# BT_AQ_DOL_R8.net
KiCad netlist of a schematic drawn in EAGLE
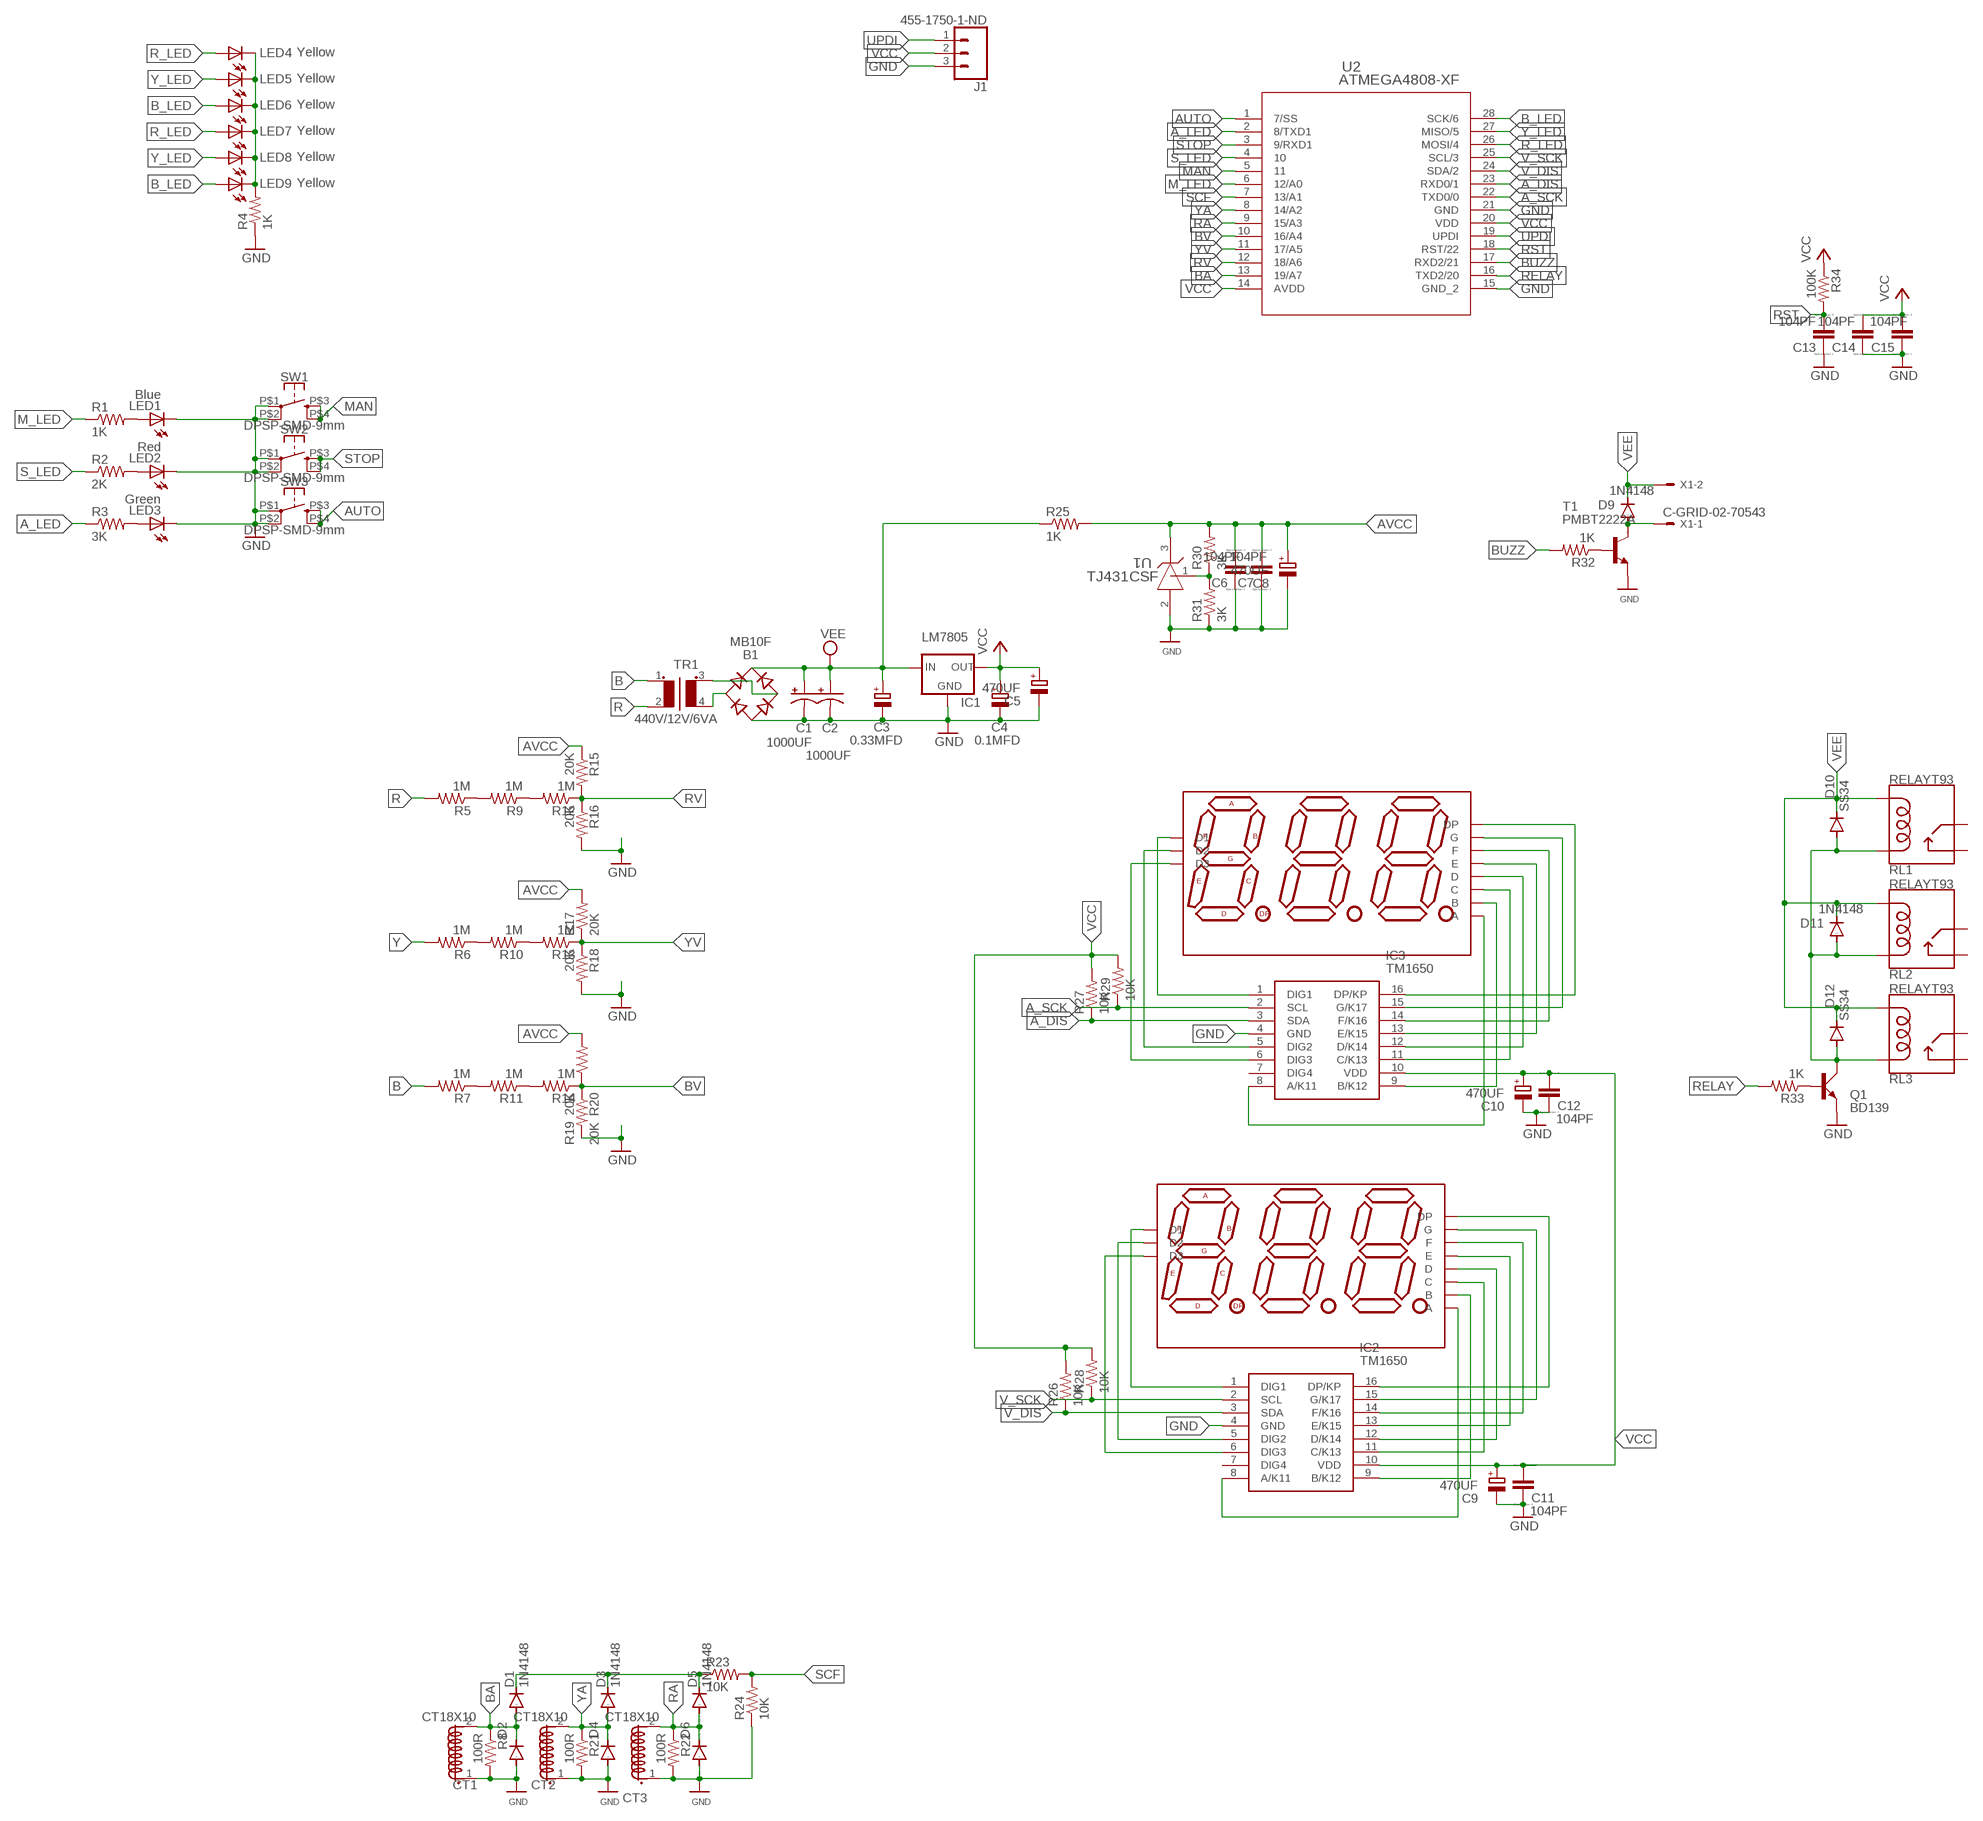
[diagram p0: schematic, sheet 1]

(export (version "E")
  (design (tool "Eeschema 10.0.6"))
  (components
    (comp (ref "B1")
      (value "MB10F")
      (footprint "eagle-import:SOIC-4")
      (libsource (lib "eagle-import") (part "MBS8"))
    )
    (comp (ref "C1")
      (value "1000UF")
      (footprint "eagle-import:E3,5-10")
      (libsource (lib "eagle-import") (part "CPOL-USE3.5-10"))
    )
    (comp (ref "C2")
      (value "1000UF")
      (footprint "eagle-import:E3,5-10")
      (libsource (lib "eagle-import") (part "CPOL-USE3.5-10"))
    )
    (comp (ref "C3")
      (value "0.33MFD")
      (footprint "eagle-import:E2,5-5")
      (libsource (lib "eagle-import") (part "CPOL-EUE2.5-5"))
    )
    (comp (ref "C4")
      (value "0.1MFD")
      (footprint "eagle-import:E2,5-5")
      (libsource (lib "eagle-import") (part "CPOL-EUE2.5-5"))
    )
    (comp (ref "C5")
      (value "470UF")
      (footprint "eagle-import:E3,5-8")
      (libsource (lib "eagle-import") (part "CPOL-EUE3.5-8"))
    )
    (comp (ref "C6")
      (value "104PF")
      (footprint "eagle-import:C1206")
      (libsource (lib "eagle-import") (part "CC1206"))
    )
    (comp (ref "C7")
      (value "104PF")
      (footprint "eagle-import:C1206")
      (libsource (lib "eagle-import") (part "CC1206"))
    )
    (comp (ref "C8")
      (value "470UF")
      (footprint "eagle-import:E3,5-8")
      (libsource (lib "eagle-import") (part "CPOL-EUE3.5-8"))
    )
    (comp (ref "C9")
      (value "470UF")
      (footprint "eagle-import:E3,5-8")
      (libsource (lib "eagle-import") (part "CPOL-EUE3.5-8"))
    )
    (comp (ref "C10")
      (value "470UF")
      (footprint "eagle-import:E3,5-8")
      (libsource (lib "eagle-import") (part "CPOL-EUE3.5-8"))
    )
    (comp (ref "C11")
      (value "104PF")
      (footprint "eagle-import:C1206")
      (libsource (lib "eagle-import") (part "CC1206"))
    )
    (comp (ref "C12")
      (value "104PF")
      (footprint "eagle-import:C1206")
      (libsource (lib "eagle-import") (part "CC1206"))
    )
    (comp (ref "C13")
      (value "104PF")
      (footprint "eagle-import:C1206")
      (libsource (lib "eagle-import") (part "CC1206"))
    )
    (comp (ref "C14")
      (value "104PF")
      (footprint "eagle-import:C1206")
      (libsource (lib "eagle-import") (part "CC1206"))
    )
    (comp (ref "C15")
      (value "104PF")
      (footprint "eagle-import:C1206")
      (libsource (lib "eagle-import") (part "CC1206"))
    )
    (comp (ref "CT1")
      (value "CT18X10")
      (footprint "eagle-import:ZMCT103C")
      (libsource (lib "eagle-import") (part "CT18X10"))
    )
    (comp (ref "CT2")
      (value "CT18X10")
      (footprint "eagle-import:ZMCT103C")
      (libsource (lib "eagle-import") (part "CT18X10"))
    )
    (comp (ref "CT3")
      (value "CT18X10")
      (footprint "eagle-import:ZMCT103C")
      (libsource (lib "eagle-import") (part "CT18X10"))
    )
    (comp (ref "D1")
      (value "1N4148")
      (footprint "eagle-import:MINIMELF")
      (libsource (lib "eagle-import") (part "DIODE-MINIMELF"))
    )
    (comp (ref "D2")
      (value "SMAJ12A")
      (footprint "eagle-import:DO214AC")
      (libsource (lib "eagle-import") (part "DIODE-DO214AC"))
    )
    (comp (ref "D3")
      (value "1N4148")
      (footprint "eagle-import:MINIMELF")
      (libsource (lib "eagle-import") (part "DIODE-MINIMELF"))
    )
    (comp (ref "D4")
      (value "SMAJ12A")
      (footprint "eagle-import:DO214AC")
      (libsource (lib "eagle-import") (part "DIODE-DO214AC"))
    )
    (comp (ref "D5")
      (value "1N4148")
      (footprint "eagle-import:MINIMELF")
      (libsource (lib "eagle-import") (part "DIODE-MINIMELF"))
    )
    (comp (ref "D6")
      (value "SMAJ12A")
      (footprint "eagle-import:DO214AC")
      (libsource (lib "eagle-import") (part "DIODE-DO214AC"))
    )
    (comp (ref "D7")
      (value "SUNR036CC3D")
      (footprint "eagle-import:7S3D036_DIP")
      (libsource (lib "eagle-import") (part "7SEGMENT-3DIGITDIP"))
    )
    (comp (ref "D8")
      (value "SUNR036CC3D")
      (footprint "eagle-import:7S3D036_DIP")
      (libsource (lib "eagle-import") (part "7SEGMENT-3DIGITDIP"))
    )
    (comp (ref "D9")
      (value "1N4148")
      (footprint "eagle-import:MINIMELF")
      (libsource (lib "eagle-import") (part "DIODE-MINIMELF"))
    )
    (comp (ref "D10")
      (value "SS34")
      (footprint "eagle-import:DO-214AC")
      (libsource (lib "eagle-import") (part "DIODE-DO-214AC"))
    )
    (comp (ref "D11")
      (value "1N4148")
      (footprint "eagle-import:MINIMELF")
      (libsource (lib "eagle-import") (part "DIODE-MINIMELF"))
    )
    (comp (ref "D12")
      (value "SS34")
      (footprint "eagle-import:DO-214AC")
      (libsource (lib "eagle-import") (part "DIODE-DO-214AC"))
    )
    (comp (ref "IC1")
      (value "LM7805")
      (footprint "eagle-import:78XXS")
      (libsource (lib "eagle-import") (part "78XXS"))
    )
    (comp (ref "IC2")
      (value "TM1650")
      (footprint "eagle-import:SOIC127P604X185-16N")
      (fields (field (name "MANUFACTURER_PART_NUMBER") "tm1650"))
      (libsource (lib "eagle-import") (part "TM1650"))
    )
    (comp (ref "IC3")
      (value "TM1650")
      (footprint "eagle-import:SOIC127P604X185-16N")
      (fields (field (name "MANUFACTURER_PART_NUMBER") "tm1650"))
      (libsource (lib "eagle-import") (part "TM1650"))
    )
    (comp (ref "J1")
      (value "455-1750-1-ND")
      (footprint "eagle-import:1X03")
      (libsource (lib "eagle-import") (part "CONN_03"))
    )
    (comp (ref "LED1")
      (value "Blue")
      (footprint "eagle-import:LED3MM")
      (libsource (lib "eagle-import") (part "LED3MM"))
    )
    (comp (ref "LED2")
      (value "Red")
      (footprint "eagle-import:LED3MM")
      (libsource (lib "eagle-import") (part "LED3MM"))
    )
    (comp (ref "LED3")
      (value "Green")
      (footprint "eagle-import:LED3MM")
      (libsource (lib "eagle-import") (part "LED3MM"))
    )
    (comp (ref "LED4")
      (value "Yellow")
      (footprint "eagle-import:LED3MM")
      (libsource (lib "eagle-import") (part "LED3MM"))
    )
    (comp (ref "LED5")
      (value "Yellow")
      (footprint "eagle-import:LED3MM")
      (libsource (lib "eagle-import") (part "LED3MM"))
    )
    (comp (ref "LED6")
      (value "Yellow")
      (footprint "eagle-import:LED3MM")
      (libsource (lib "eagle-import") (part "LED3MM"))
    )
    (comp (ref "LED7")
      (value "Yellow")
      (footprint "eagle-import:LED3MM")
      (libsource (lib "eagle-import") (part "LED3MM"))
    )
    (comp (ref "LED8")
      (value "Yellow")
      (footprint "eagle-import:LED3MM")
      (libsource (lib "eagle-import") (part "LED3MM"))
    )
    (comp (ref "LED9")
      (value "Yellow")
      (footprint "eagle-import:LED3MM")
      (libsource (lib "eagle-import") (part "LED3MM"))
    )
    (comp (ref "Q1")
      (value "BD139")
      (footprint "eagle-import:TO126AV")
      (libsource (lib "eagle-import") (part "BD139"))
    )
    (comp (ref "R1")
      (value "1K")
      (footprint "eagle-import:M1206")
      (libsource (lib "eagle-import") (part "rcl_334_R-US_M1206"))
    )
    (comp (ref "R2")
      (value "2K")
      (footprint "eagle-import:M1206")
      (libsource (lib "eagle-import") (part "rcl_334_R-US_M1206"))
    )
    (comp (ref "R3")
      (value "3K")
      (footprint "eagle-import:M1206")
      (libsource (lib "eagle-import") (part "rcl_334_R-US_M1206"))
    )
    (comp (ref "R4")
      (value "1K")
      (footprint "eagle-import:M1206")
      (libsource (lib "eagle-import") (part "rcl_334_R-US_M1206"))
    )
    (comp (ref "R5")
      (value "1M")
      (footprint "eagle-import:M1206")
      (libsource (lib "eagle-import") (part "rcl_334_R-US_M1206"))
    )
    (comp (ref "R6")
      (value "1M")
      (footprint "eagle-import:M1206")
      (libsource (lib "eagle-import") (part "rcl_334_R-US_M1206"))
    )
    (comp (ref "R7")
      (value "1M")
      (footprint "eagle-import:M1206")
      (libsource (lib "eagle-import") (part "rcl_334_R-US_M1206"))
    )
    (comp (ref "R8")
      (value "100R")
      (footprint "eagle-import:M1206")
      (libsource (lib "eagle-import") (part "R-US_M1206"))
    )
    (comp (ref "R9")
      (value "1M")
      (footprint "eagle-import:M1206")
      (libsource (lib "eagle-import") (part "rcl_334_R-US_M1206"))
    )
    (comp (ref "R10")
      (value "1M")
      (footprint "eagle-import:M1206")
      (libsource (lib "eagle-import") (part "rcl_334_R-US_M1206"))
    )
    (comp (ref "R11")
      (value "1M")
      (footprint "eagle-import:M1206")
      (libsource (lib "eagle-import") (part "rcl_334_R-US_M1206"))
    )
    (comp (ref "R12")
      (value "1M")
      (footprint "eagle-import:M1206")
      (libsource (lib "eagle-import") (part "rcl_334_R-US_M1206"))
    )
    (comp (ref "R13")
      (value "1M")
      (footprint "eagle-import:M1206")
      (libsource (lib "eagle-import") (part "rcl_334_R-US_M1206"))
    )
    (comp (ref "R14")
      (value "1M")
      (footprint "eagle-import:M1206")
      (libsource (lib "eagle-import") (part "rcl_334_R-US_M1206"))
    )
    (comp (ref "R15")
      (value "20K")
      (footprint "eagle-import:M1206")
      (libsource (lib "eagle-import") (part "rcl_334_R-US_M1206"))
    )
    (comp (ref "R16")
      (value "20K")
      (footprint "eagle-import:M1206")
      (libsource (lib "eagle-import") (part "rcl_334_R-US_M1206"))
    )
    (comp (ref "R17")
      (value "20K")
      (footprint "eagle-import:M1206")
      (libsource (lib "eagle-import") (part "rcl_334_R-US_M1206"))
    )
    (comp (ref "R18")
      (value "20K")
      (footprint "eagle-import:M1206")
      (libsource (lib "eagle-import") (part "rcl_334_R-US_M1206"))
    )
    (comp (ref "R19")
      (value "20K")
      (footprint "eagle-import:M1206")
      (libsource (lib "eagle-import") (part "rcl_334_R-US_M1206"))
    )
    (comp (ref "R20")
      (value "20K")
      (footprint "eagle-import:M1206")
      (libsource (lib "eagle-import") (part "rcl_334_R-US_M1206"))
    )
    (comp (ref "R21")
      (value "100R")
      (footprint "eagle-import:M1206")
      (libsource (lib "eagle-import") (part "R-US_M1206"))
    )
    (comp (ref "R22")
      (value "100R")
      (footprint "eagle-import:M1206")
      (libsource (lib "eagle-import") (part "R-US_M1206"))
    )
    (comp (ref "R23")
      (value "10K")
      (footprint "eagle-import:M1206")
      (libsource (lib "eagle-import") (part "R-US_M1206"))
    )
    (comp (ref "R24")
      (value "10K")
      (footprint "eagle-import:M1206")
      (libsource (lib "eagle-import") (part "R-US_M1206"))
    )
    (comp (ref "R25")
      (value "1K")
      (footprint "eagle-import:M1206")
      (libsource (lib "eagle-import") (part "R-US_M1206"))
    )
    (comp (ref "R26")
      (value "10K")
      (footprint "eagle-import:M1206")
      (libsource (lib "eagle-import") (part "rcl_334_R-US_M1206"))
    )
    (comp (ref "R27")
      (value "10K")
      (footprint "eagle-import:M1206")
      (libsource (lib "eagle-import") (part "rcl_334_R-US_M1206"))
    )
    (comp (ref "R28")
      (value "10K")
      (footprint "eagle-import:M1206")
      (libsource (lib "eagle-import") (part "rcl_334_R-US_M1206"))
    )
    (comp (ref "R29")
      (value "10K")
      (footprint "eagle-import:M1206")
      (libsource (lib "eagle-import") (part "rcl_334_R-US_M1206"))
    )
    (comp (ref "R30")
      (value "3K")
      (footprint "eagle-import:M1206")
      (libsource (lib "eagle-import") (part "R-US_M1206"))
    )
    (comp (ref "R31")
      (value "3K")
      (footprint "eagle-import:M1206")
      (libsource (lib "eagle-import") (part "R-US_M1206"))
    )
    (comp (ref "R32")
      (value "1K")
      (footprint "eagle-import:M1206")
      (libsource (lib "eagle-import") (part "rcl_334_R-US_M1206"))
    )
    (comp (ref "R33")
      (value "1K")
      (footprint "eagle-import:M1206")
      (libsource (lib "eagle-import") (part "rcl_334_R-US_M1206"))
    )
    (comp (ref "R34")
      (value "100K")
      (footprint "eagle-import:M1206")
      (libsource (lib "eagle-import") (part "rcl_334_R-US_M1206"))
    )
    (comp (ref "RL1")
      (value "RELAYT93")
      (footprint "eagle-import:DT93")
      (libsource (lib "eagle-import") (part "RELAYT93"))
    )
    (comp (ref "RL2")
      (value "RELAYT93")
      (footprint "eagle-import:DT93")
      (libsource (lib "eagle-import") (part "RELAYT93"))
    )
    (comp (ref "RL3")
      (value "RELAYT93")
      (footprint "eagle-import:DT93")
      (libsource (lib "eagle-import") (part "RELAYT93"))
    )
    (comp (ref "SW1")
      (value "DPSP-SMD-9mm")
      (footprint "eagle-import:B3F-40XX-ROUND-SMD")
      (libsource (lib "eagle-import") (part "DPSP-SMD"))
    )
    (comp (ref "SW2")
      (value "DPSP-SMD-9mm")
      (footprint "eagle-import:B3F-40XX-ROUND-SMD")
      (libsource (lib "eagle-import") (part "DPSP-SMD"))
    )
    (comp (ref "SW3")
      (value "DPSP-SMD-9mm")
      (footprint "eagle-import:B3F-40XX-ROUND-SMD")
      (libsource (lib "eagle-import") (part "DPSP-SMD"))
    )
    (comp (ref "T1")
      (value "PMBT2222A")
      (footprint "eagle-import:SC59-BEC")
      (libsource (lib "eagle-import") (part "-NPN-SC59-BECMMUN2213LT1"))
    )
    (comp (ref "TR1")
      (value "440V/12V/6VA")
      (footprint "eagle-import:440V12V6VA")
      (libsource (lib "eagle-import") (part "TRANSFORMER6VA"))
    )
    (comp (ref "U1")
      (value "TJ431CSF")
      (footprint "eagle-import:SOT-23")
      (fields
        (field (name "MANUFACTURER_PART_NUMBER") "TL431IDBZTG4")
        (field (name "COPYRIGHT") "Copyright (C) 2022 Ultra Librarian. All rights reserved.")
      )
      (libsource (lib "eagle-import") (part "TJ431CSFDBZ0003A_L"))
    )
    (comp (ref "U2")
      (value "ATMEGA4808-XF")
      (footprint "eagle-import:SSOP28_SS_MCH")
      (fields (field (name "COPYRIGHT") "Copyright (C) 2022 Ultra Librarian. All rights reserved."))
      (libsource (lib "eagle-import") (part "ATMEGA4808-XF"))
    )
    (comp (ref "X1")
      (value "C-GRID-02-70543")
      (footprint "eagle-import:70543-02")
      (fields (field (name "MF") "MOLEX"))
      (libsource (lib "eagle-import") (part "C-GRID-02-70543"))
    )
  )
  (nets
    (net (code "1") (name "AUTO") (class "Default")
      (node (ref "SW3") (pin "P$3") (pinfunction "3_P$3") (pintype "passive"))
      (node (ref "SW3") (pin "P$4") (pinfunction "4_P$4") (pintype "passive"))
      (node (ref "U2") (pin "1") (pinfunction "7/SS_1") (pintype "bidirectional"))
    )
    (net (code "2") (name "AVCC") (class "Default")
      (node (ref "C6") (pin "2") (pinfunction "2_2") (pintype "passive"))
      (node (ref "C7") (pin "2") (pinfunction "2_2") (pintype "passive"))
      (node (ref "C8") (pin "+") (pinfunction "+_+") (pintype "passive"))
      (node (ref "R15") (pin "1") (pinfunction "1_1") (pintype "passive"))
      (node (ref "R17") (pin "2") (pinfunction "2_2") (pintype "passive"))
      (node (ref "R19") (pin "2") (pinfunction "2_2") (pintype "passive"))
      (node (ref "R25") (pin "2") (pinfunction "2_2") (pintype "passive"))
      (node (ref "R30") (pin "2") (pinfunction "2_2") (pintype "passive"))
      (node (ref "U1") (pin "3") (pinfunction "CATHODE_3") (pintype "passive"))
    )
    (net (code "3") (name "A_DIS") (class "Default")
      (node (ref "IC3") (pin "3") (pinfunction "SDA_3") (pintype "input"))
      (node (ref "R27") (pin "1") (pinfunction "1_1") (pintype "passive"))
      (node (ref "U2") (pin "23") (pinfunction "RXD0/1_23") (pintype "bidirectional"))
    )
    (net (code "4") (name "A_LED") (class "Default")
      (node (ref "R3") (pin "1") (pinfunction "1_1") (pintype "passive"))
      (node (ref "U2") (pin "2") (pinfunction "8/TXD1_2") (pintype "bidirectional"))
    )
    (net (code "5") (name "A_SCK") (class "Default")
      (node (ref "IC3") (pin "2") (pinfunction "SCL_2") (pintype "input"))
      (node (ref "R29") (pin "1") (pinfunction "1_1") (pintype "passive"))
      (node (ref "U2") (pin "22") (pinfunction "TXD0/0_22") (pintype "bidirectional"))
    )
    (net (code "6") (name "B") (class "Default")
      (node (ref "R7") (pin "2") (pinfunction "2_2") (pintype "passive"))
      (node (ref "TR1") (pin "1") (pinfunction "P1_1") (pintype "passive"))
    )
    (net (code "7") (name "BA") (class "Default")
      (node (ref "CT1") (pin "2") (pinfunction "S1.2_2") (pintype "passive"))
      (node (ref "D1") (pin "A") (pinfunction "A_A") (pintype "passive"))
      (node (ref "D2") (pin "C") (pinfunction "C_C") (pintype "passive"))
      (node (ref "R8") (pin "1") (pinfunction "1_1") (pintype "passive"))
      (node (ref "U2") (pin "13") (pinfunction "19/A7_13") (pintype "bidirectional"))
    )
    (net (code "8") (name "BUZZ") (class "Default")
      (node (ref "R32") (pin "2") (pinfunction "2_2") (pintype "passive"))
      (node (ref "U2") (pin "17") (pinfunction "RXD2/21_17") (pintype "bidirectional"))
    )
    (net (code "9") (name "BV") (class "Default")
      (node (ref "R14") (pin "1") (pinfunction "1_1") (pintype "passive"))
      (node (ref "R19") (pin "1") (pinfunction "1_1") (pintype "passive"))
      (node (ref "R20") (pin "1") (pinfunction "1_1") (pintype "passive"))
      (node (ref "U2") (pin "10") (pinfunction "16/A4_10") (pintype "bidirectional"))
    )
    (net (code "10") (name "B_LED") (class "Default")
      (node (ref "LED6") (pin "A") (pinfunction "A_A") (pintype "passive"))
      (node (ref "LED9") (pin "A") (pinfunction "A_A") (pintype "passive"))
      (node (ref "U2") (pin "28") (pinfunction "SCK/6_28") (pintype "bidirectional"))
    )
    (net (code "11") (name "GND") (class "Default")
      (node (ref "B1") (pin "-") (pinfunction "-_-") (pintype "passive"))
      (node (ref "C1") (pin "-") (pinfunction "-_-") (pintype "passive"))
      (node (ref "C10") (pin "-") (pinfunction "-_-") (pintype "passive"))
      (node (ref "C11") (pin "1") (pinfunction "1_1") (pintype "passive"))
      (node (ref "C12") (pin "1") (pinfunction "1_1") (pintype "passive"))
      (node (ref "C13") (pin "1") (pinfunction "1_1") (pintype "passive"))
      (node (ref "C14") (pin "1") (pinfunction "1_1") (pintype "passive"))
      (node (ref "C15") (pin "1") (pinfunction "1_1") (pintype "passive"))
      (node (ref "C2") (pin "-") (pinfunction "-_-") (pintype "passive"))
      (node (ref "C3") (pin "-") (pinfunction "-_-") (pintype "passive"))
      (node (ref "C4") (pin "-") (pinfunction "-_-") (pintype "passive"))
      (node (ref "C5") (pin "-") (pinfunction "-_-") (pintype "passive"))
      (node (ref "C6") (pin "1") (pinfunction "1_1") (pintype "passive"))
      (node (ref "C7") (pin "1") (pinfunction "1_1") (pintype "passive"))
      (node (ref "C8") (pin "-") (pinfunction "-_-") (pintype "passive"))
      (node (ref "C9") (pin "-") (pinfunction "-_-") (pintype "passive"))
      (node (ref "CT1") (pin "1") (pinfunction "S1.1_1") (pintype "passive"))
      (node (ref "CT2") (pin "1") (pinfunction "S1.1_1") (pintype "passive"))
      (node (ref "CT3") (pin "1") (pinfunction "S1.1_1") (pintype "passive"))
      (node (ref "D2") (pin "A") (pinfunction "A_A") (pintype "passive"))
      (node (ref "D4") (pin "A") (pinfunction "A_A") (pintype "passive"))
      (node (ref "D6") (pin "A") (pinfunction "A_A") (pintype "passive"))
      (node (ref "IC1") (pin "GND") (pinfunction "GND_GND") (pintype "input"))
      (node (ref "IC2") (pin "4") (pinfunction "GND_4") (pintype "power_in"))
      (node (ref "IC3") (pin "4") (pinfunction "GND_4") (pintype "power_in"))
      (node (ref "J1") (pin "3") (pinfunction "3_3") (pintype "passive"))
      (node (ref "LED1") (pin "K") (pinfunction "C_K") (pintype "passive"))
      (node (ref "LED2") (pin "K") (pinfunction "C_K") (pintype "passive"))
      (node (ref "LED3") (pin "K") (pinfunction "C_K") (pintype "passive"))
      (node (ref "Q1") (pin "E") (pinfunction "E_E") (pintype "passive"))
      (node (ref "R16") (pin "2") (pinfunction "2_2") (pintype "passive"))
      (node (ref "R18") (pin "2") (pinfunction "2_2") (pintype "passive"))
      (node (ref "R20") (pin "2") (pinfunction "2_2") (pintype "passive"))
      (node (ref "R21") (pin "2") (pinfunction "2_2") (pintype "passive"))
      (node (ref "R22") (pin "2") (pinfunction "2_2") (pintype "passive"))
      (node (ref "R24") (pin "1") (pinfunction "1_1") (pintype "passive"))
      (node (ref "R31") (pin "1") (pinfunction "1_1") (pintype "passive"))
      (node (ref "R4") (pin "1") (pinfunction "1_1") (pintype "passive"))
      (node (ref "R8") (pin "2") (pinfunction "2_2") (pintype "passive"))
      (node (ref "SW1") (pin "P$1") (pinfunction "1_P$1") (pintype "passive"))
      (node (ref "SW1") (pin "P$2") (pinfunction "2_P$2") (pintype "passive"))
      (node (ref "SW2") (pin "P$1") (pinfunction "1_P$1") (pintype "passive"))
      (node (ref "SW2") (pin "P$2") (pinfunction "2_P$2") (pintype "passive"))
      (node (ref "SW3") (pin "P$1") (pinfunction "1_P$1") (pintype "passive"))
      (node (ref "SW3") (pin "P$2") (pinfunction "2_P$2") (pintype "passive"))
      (node (ref "T1") (pin "E") (pinfunction "E_E") (pintype "passive"))
      (node (ref "U1") (pin "2") (pinfunction "ANODE_2") (pintype "passive"))
      (node (ref "U2") (pin "15") (pinfunction "GND_2_15") (pintype "passive"))
      (node (ref "U2") (pin "21") (pinfunction "GND_21") (pintype "passive"))
    )
    (net (code "12") (name "MAN") (class "Default")
      (node (ref "SW1") (pin "P$3") (pinfunction "3_P$3") (pintype "passive"))
      (node (ref "SW1") (pin "P$4") (pinfunction "4_P$4") (pintype "passive"))
      (node (ref "U2") (pin "5") (pinfunction "11_5") (pintype "bidirectional"))
    )
    (net (code "13") (name "M_LED") (class "Default")
      (node (ref "R1") (pin "1") (pinfunction "1_1") (pintype "passive"))
      (node (ref "U2") (pin "6") (pinfunction "12/A0_6") (pintype "bidirectional"))
    )
    (net (code "14") (name "Net-(B1-AC1)") (class "Default")
      (node (ref "B1") (pin "~1") (pinfunction "AC1_~1") (pintype "passive"))
      (node (ref "TR1") (pin "4") (pinfunction "S2_4") (pintype "passive"))
    )
    (net (code "15") (name "Net-(B1-AC2)") (class "Default")
      (node (ref "B1") (pin "~2") (pinfunction "AC2_~2") (pintype "passive"))
      (node (ref "TR1") (pin "3") (pinfunction "S1_3") (pintype "passive"))
    )
    (net (code "16") (name "Net-(D1-PadC)") (class "Default")
      (node (ref "D1") (pin "C") (pinfunction "C_C") (pintype "passive"))
      (node (ref "D3") (pin "C") (pinfunction "C_C") (pintype "passive"))
      (node (ref "D5") (pin "C") (pinfunction "C_C") (pintype "passive"))
      (node (ref "R23") (pin "1") (pinfunction "1_1") (pintype "passive"))
    )
    (net (code "17") (name "Net-(D7-A)") (class "Default")
      (node (ref "D7") (pin "11") (pinfunction "A_11") (pintype "bidirectional"))
      (node (ref "IC2") (pin "8") (pinfunction "A/K11_8") (pintype "bidirectional"))
    )
    (net (code "18") (name "Net-(D7-B)") (class "Default")
      (node (ref "D7") (pin "7") (pinfunction "B_7") (pintype "bidirectional"))
      (node (ref "IC2") (pin "9") (pinfunction "B/K12_9") (pintype "bidirectional"))
    )
    (net (code "19") (name "Net-(D7-C)") (class "Default")
      (node (ref "D7") (pin "4") (pinfunction "C_4") (pintype "bidirectional"))
      (node (ref "IC2") (pin "11") (pinfunction "C/K13_11") (pintype "bidirectional"))
    )
    (net (code "20") (name "Net-(D7-D)") (class "Default")
      (node (ref "D7") (pin "2") (pinfunction "D_2") (pintype "bidirectional"))
      (node (ref "IC2") (pin "12") (pinfunction "D/K14_12") (pintype "bidirectional"))
    )
    (net (code "21") (name "Net-(D7-D1)") (class "Default")
      (node (ref "D7") (pin "12") (pinfunction "D1_12") (pintype "bidirectional"))
      (node (ref "IC2") (pin "1") (pinfunction "DIG1_1") (pintype "bidirectional"))
    )
    (net (code "22") (name "Net-(D7-D2)") (class "Default")
      (node (ref "D7") (pin "9") (pinfunction "D2_9") (pintype "bidirectional"))
      (node (ref "IC2") (pin "5") (pinfunction "DIG2_5") (pintype "bidirectional"))
    )
    (net (code "23") (name "Net-(D7-D3)") (class "Default")
      (node (ref "D7") (pin "8") (pinfunction "D3_8") (pintype "bidirectional"))
      (node (ref "IC2") (pin "6") (pinfunction "DIG3_6") (pintype "bidirectional"))
    )
    (net (code "24") (name "Net-(D7-DP)") (class "Default")
      (node (ref "D7") (pin "3") (pinfunction "DP_3") (pintype "bidirectional"))
      (node (ref "IC2") (pin "16") (pinfunction "DP/KP_16") (pintype "bidirectional"))
    )
    (net (code "25") (name "Net-(D7-E)") (class "Default")
      (node (ref "D7") (pin "1") (pinfunction "E_1") (pintype "bidirectional"))
      (node (ref "IC2") (pin "13") (pinfunction "E/K15_13") (pintype "bidirectional"))
    )
    (net (code "26") (name "Net-(D7-F)") (class "Default")
      (node (ref "D7") (pin "10") (pinfunction "F_10") (pintype "bidirectional"))
      (node (ref "IC2") (pin "14") (pinfunction "F/K16_14") (pintype "bidirectional"))
    )
    (net (code "27") (name "Net-(D7-G)") (class "Default")
      (node (ref "D7") (pin "5") (pinfunction "G_5") (pintype "bidirectional"))
      (node (ref "IC2") (pin "15") (pinfunction "G/K17_15") (pintype "bidirectional"))
    )
    (net (code "28") (name "Net-(D8-A)") (class "Default")
      (node (ref "D8") (pin "11") (pinfunction "A_11") (pintype "bidirectional"))
      (node (ref "IC3") (pin "8") (pinfunction "A/K11_8") (pintype "bidirectional"))
    )
    (net (code "29") (name "Net-(D8-B)") (class "Default")
      (node (ref "D8") (pin "7") (pinfunction "B_7") (pintype "bidirectional"))
      (node (ref "IC3") (pin "9") (pinfunction "B/K12_9") (pintype "bidirectional"))
    )
    (net (code "30") (name "Net-(D8-C)") (class "Default")
      (node (ref "D8") (pin "4") (pinfunction "C_4") (pintype "bidirectional"))
      (node (ref "IC3") (pin "11") (pinfunction "C/K13_11") (pintype "bidirectional"))
    )
    (net (code "31") (name "Net-(D8-D)") (class "Default")
      (node (ref "D8") (pin "2") (pinfunction "D_2") (pintype "bidirectional"))
      (node (ref "IC3") (pin "12") (pinfunction "D/K14_12") (pintype "bidirectional"))
    )
    (net (code "32") (name "Net-(D8-D1)") (class "Default")
      (node (ref "D8") (pin "12") (pinfunction "D1_12") (pintype "bidirectional"))
      (node (ref "IC3") (pin "1") (pinfunction "DIG1_1") (pintype "bidirectional"))
    )
    (net (code "33") (name "Net-(D8-D2)") (class "Default")
      (node (ref "D8") (pin "9") (pinfunction "D2_9") (pintype "bidirectional"))
      (node (ref "IC3") (pin "5") (pinfunction "DIG2_5") (pintype "bidirectional"))
    )
    (net (code "34") (name "Net-(D8-D3)") (class "Default")
      (node (ref "D8") (pin "8") (pinfunction "D3_8") (pintype "bidirectional"))
      (node (ref "IC3") (pin "6") (pinfunction "DIG3_6") (pintype "bidirectional"))
    )
    (net (code "35") (name "Net-(D8-DP)") (class "Default")
      (node (ref "D8") (pin "3") (pinfunction "DP_3") (pintype "bidirectional"))
      (node (ref "IC3") (pin "16") (pinfunction "DP/KP_16") (pintype "bidirectional"))
    )
    (net (code "36") (name "Net-(D8-E)") (class "Default")
      (node (ref "D8") (pin "1") (pinfunction "E_1") (pintype "bidirectional"))
      (node (ref "IC3") (pin "13") (pinfunction "E/K15_13") (pintype "bidirectional"))
    )
    (net (code "37") (name "Net-(D8-F)") (class "Default")
      (node (ref "D8") (pin "10") (pinfunction "F_10") (pintype "bidirectional"))
      (node (ref "IC3") (pin "14") (pinfunction "F/K16_14") (pintype "bidirectional"))
    )
    (net (code "38") (name "Net-(D8-G)") (class "Default")
      (node (ref "D8") (pin "5") (pinfunction "G_5") (pintype "bidirectional"))
      (node (ref "IC3") (pin "15") (pinfunction "G/K17_15") (pintype "bidirectional"))
    )
    (net (code "39") (name "Net-(LED1-PadA)") (class "Default")
      (node (ref "LED1") (pin "A") (pinfunction "A_A") (pintype "passive"))
      (node (ref "R1") (pin "2") (pinfunction "2_2") (pintype "passive"))
    )
    (net (code "40") (name "Net-(LED2-PadA)") (class "Default")
      (node (ref "LED2") (pin "A") (pinfunction "A_A") (pintype "passive"))
      (node (ref "R2") (pin "2") (pinfunction "2_2") (pintype "passive"))
    )
    (net (code "41") (name "Net-(LED3-PadA)") (class "Default")
      (node (ref "LED3") (pin "A") (pinfunction "A_A") (pintype "passive"))
      (node (ref "R3") (pin "2") (pinfunction "2_2") (pintype "passive"))
    )
    (net (code "42") (name "Net-(LED4-C)") (class "Default")
      (node (ref "LED4") (pin "K") (pinfunction "C_K") (pintype "passive"))
      (node (ref "LED5") (pin "K") (pinfunction "C_K") (pintype "passive"))
      (node (ref "LED6") (pin "K") (pinfunction "C_K") (pintype "passive"))
      (node (ref "LED7") (pin "K") (pinfunction "C_K") (pintype "passive"))
      (node (ref "LED8") (pin "K") (pinfunction "C_K") (pintype "passive"))
      (node (ref "LED9") (pin "K") (pinfunction "C_K") (pintype "passive"))
      (node (ref "R4") (pin "2") (pinfunction "2_2") (pintype "passive"))
    )
    (net (code "43") (name "Net-(Q1-PadB)") (class "Default")
      (node (ref "Q1") (pin "B") (pinfunction "B_B") (pintype "passive"))
      (node (ref "R33") (pin "1") (pinfunction "1_1") (pintype "passive"))
    )
    (net (code "44") (name "Net-(R5-Pad1)") (class "Default")
      (node (ref "R5") (pin "1") (pinfunction "1_1") (pintype "passive"))
      (node (ref "R9") (pin "2") (pinfunction "2_2") (pintype "passive"))
    )
    (net (code "45") (name "Net-(R10-Pad1)") (class "Default")
      (node (ref "R10") (pin "1") (pinfunction "1_1") (pintype "passive"))
      (node (ref "R13") (pin "2") (pinfunction "2_2") (pintype "passive"))
    )
    (net (code "46") (name "Net-(R10-Pad2)") (class "Default")
      (node (ref "R10") (pin "2") (pinfunction "2_2") (pintype "passive"))
      (node (ref "R6") (pin "1") (pinfunction "1_1") (pintype "passive"))
    )
    (net (code "47") (name "Net-(R11-Pad1)") (class "Default")
      (node (ref "R11") (pin "1") (pinfunction "1_1") (pintype "passive"))
      (node (ref "R14") (pin "2") (pinfunction "2_2") (pintype "passive"))
    )
    (net (code "48") (name "Net-(R11-Pad2)") (class "Default")
      (node (ref "R11") (pin "2") (pinfunction "2_2") (pintype "passive"))
      (node (ref "R7") (pin "1") (pinfunction "1_1") (pintype "passive"))
    )
    (net (code "49") (name "Net-(R12-Pad2)") (class "Default")
      (node (ref "R12") (pin "2") (pinfunction "2_2") (pintype "passive"))
      (node (ref "R9") (pin "1") (pinfunction "1_1") (pintype "passive"))
    )
    (net (code "50") (name "Net-(R32-Pad1)") (class "Default")
      (node (ref "R32") (pin "1") (pinfunction "1_1") (pintype "passive"))
      (node (ref "T1") (pin "B") (pinfunction "B_B") (pintype "passive"))
    )
    (net (code "51") (name "Net-(RL1-COIL1)") (class "Default")
      (node (ref "D10") (pin "A") (pinfunction "A_A") (pintype "passive"))
      (node (ref "D11") (pin "A") (pinfunction "A_A") (pintype "passive"))
      (node (ref "D12") (pin "A") (pinfunction "A_A") (pintype "passive"))
      (node (ref "Q1") (pin "C") (pinfunction "C_C") (pintype "passive"))
      (node (ref "RL1") (pin "A1") (pinfunction "COIL1_A1") (pintype "bidirectional"))
      (node (ref "RL2") (pin "A1") (pinfunction "COIL1_A1") (pintype "bidirectional"))
      (node (ref "RL3") (pin "A1") (pinfunction "COIL1_A1") (pintype "bidirectional"))
    )
    (net (code "52") (name "Net-(U1-REF)") (class "Default")
      (node (ref "R30") (pin "1") (pinfunction "1_1") (pintype "passive"))
      (node (ref "R31") (pin "2") (pinfunction "2_2") (pintype "passive"))
      (node (ref "U1") (pin "1") (pinfunction "REF_1") (pintype "input"))
    )
    (net (code "53") (name "Net-(X1A-S)") (class "Default")
      (node (ref "D9") (pin "A") (pinfunction "A_A") (pintype "passive"))
      (node (ref "T1") (pin "C") (pinfunction "C_C") (pintype "passive"))
      (node (ref "X1") (pin "1") (pinfunction "S_1") (pintype "passive"))
    )
    (net (code "54") (name "R") (class "Default")
      (node (ref "R5") (pin "2") (pinfunction "2_2") (pintype "passive"))
      (node (ref "TR1") (pin "2") (pinfunction "P2_2") (pintype "passive"))
    )
    (net (code "55") (name "RA") (class "Default")
      (node (ref "CT3") (pin "2") (pinfunction "S1.2_2") (pintype "passive"))
      (node (ref "D5") (pin "A") (pinfunction "A_A") (pintype "passive"))
      (node (ref "D6") (pin "C") (pinfunction "C_C") (pintype "passive"))
      (node (ref "R22") (pin "1") (pinfunction "1_1") (pintype "passive"))
      (node (ref "U2") (pin "9") (pinfunction "15/A3_9") (pintype "bidirectional"))
    )
    (net (code "56") (name "RELAY") (class "Default")
      (node (ref "R33") (pin "2") (pinfunction "2_2") (pintype "passive"))
      (node (ref "U2") (pin "16") (pinfunction "TXD2/20_16") (pintype "bidirectional"))
    )
    (net (code "57") (name "RST") (class "Default")
      (node (ref "C13") (pin "2") (pinfunction "2_2") (pintype "passive"))
      (node (ref "R34") (pin "2") (pinfunction "2_2") (pintype "passive"))
      (node (ref "U2") (pin "18") (pinfunction "RST/22_18") (pintype "bidirectional"))
    )
    (net (code "58") (name "RV") (class "Default")
      (node (ref "R12") (pin "1") (pinfunction "1_1") (pintype "passive"))
      (node (ref "R15") (pin "2") (pinfunction "2_2") (pintype "passive"))
      (node (ref "R16") (pin "1") (pinfunction "1_1") (pintype "passive"))
      (node (ref "U2") (pin "12") (pinfunction "18/A6_12") (pintype "bidirectional"))
    )
    (net (code "59") (name "R_LED") (class "Default")
      (node (ref "LED4") (pin "A") (pinfunction "A_A") (pintype "passive"))
      (node (ref "LED7") (pin "A") (pinfunction "A_A") (pintype "passive"))
      (node (ref "U2") (pin "26") (pinfunction "MOSI/4_26") (pintype "bidirectional"))
    )
    (net (code "60") (name "SCF") (class "Default")
      (node (ref "R23") (pin "2") (pinfunction "2_2") (pintype "passive"))
      (node (ref "R24") (pin "2") (pinfunction "2_2") (pintype "passive"))
      (node (ref "U2") (pin "7") (pinfunction "13/A1_7") (pintype "bidirectional"))
    )
    (net (code "61") (name "STOP") (class "Default")
      (node (ref "SW2") (pin "P$3") (pinfunction "3_P$3") (pintype "passive"))
      (node (ref "SW2") (pin "P$4") (pinfunction "4_P$4") (pintype "passive"))
      (node (ref "U2") (pin "3") (pinfunction "9/RXD1_3") (pintype "bidirectional"))
    )
    (net (code "62") (name "S_LED") (class "Default")
      (node (ref "R2") (pin "1") (pinfunction "1_1") (pintype "passive"))
      (node (ref "U2") (pin "4") (pinfunction "10_4") (pintype "bidirectional"))
    )
    (net (code "63") (name "UPDI") (class "Default")
      (node (ref "J1") (pin "1") (pinfunction "1_1") (pintype "passive"))
      (node (ref "U2") (pin "19") (pinfunction "UPDI_19") (pintype "bidirectional"))
    )
    (net (code "64") (name "VCC") (class "Default")
      (node (ref "C10") (pin "+") (pinfunction "+_+") (pintype "passive"))
      (node (ref "C11") (pin "2") (pinfunction "2_2") (pintype "passive"))
      (node (ref "C12") (pin "2") (pinfunction "2_2") (pintype "passive"))
      (node (ref "C14") (pin "2") (pinfunction "2_2") (pintype "passive"))
      (node (ref "C15") (pin "2") (pinfunction "2_2") (pintype "passive"))
      (node (ref "C4") (pin "+") (pinfunction "+_+") (pintype "passive"))
      (node (ref "C5") (pin "+") (pinfunction "+_+") (pintype "passive"))
      (node (ref "C9") (pin "+") (pinfunction "+_+") (pintype "passive"))
      (node (ref "IC1") (pin "OUT") (pinfunction "OUT_OUT") (pintype "passive"))
      (node (ref "IC2") (pin "10") (pinfunction "VDD_10") (pintype "power_in"))
      (node (ref "IC3") (pin "10") (pinfunction "VDD_10") (pintype "power_in"))
      (node (ref "J1") (pin "2") (pinfunction "2_2") (pintype "passive"))
      (node (ref "R26") (pin "2") (pinfunction "2_2") (pintype "passive"))
      (node (ref "R27") (pin "2") (pinfunction "2_2") (pintype "passive"))
      (node (ref "R28") (pin "2") (pinfunction "2_2") (pintype "passive"))
      (node (ref "R29") (pin "2") (pinfunction "2_2") (pintype "passive"))
      (node (ref "R34") (pin "1") (pinfunction "1_1") (pintype "passive"))
      (node (ref "U2") (pin "14") (pinfunction "AVDD_14") (pintype "power_in"))
      (node (ref "U2") (pin "20") (pinfunction "VDD_20") (pintype "power_in"))
    )
    (net (code "65") (name "VEE") (class "Default")
      (node (ref "B1") (pin "+") (pinfunction "+_+") (pintype "passive"))
      (node (ref "C1") (pin "+") (pinfunction "+_+") (pintype "passive"))
      (node (ref "C2") (pin "+") (pinfunction "+_+") (pintype "passive"))
      (node (ref "C3") (pin "+") (pinfunction "+_+") (pintype "passive"))
      (node (ref "D10") (pin "C") (pinfunction "C_C") (pintype "passive"))
      (node (ref "D11") (pin "C") (pinfunction "C_C") (pintype "passive"))
      (node (ref "D12") (pin "C") (pinfunction "C_C") (pintype "passive"))
      (node (ref "D9") (pin "C") (pinfunction "C_C") (pintype "passive"))
      (node (ref "IC1") (pin "IN") (pinfunction "IN_IN") (pintype "input"))
      (node (ref "R25") (pin "1") (pinfunction "1_1") (pintype "passive"))
      (node (ref "RL1") (pin "A2") (pinfunction "COIL2_A2") (pintype "bidirectional"))
      (node (ref "RL2") (pin "A2") (pinfunction "COIL2_A2") (pintype "bidirectional"))
      (node (ref "RL3") (pin "A2") (pinfunction "COIL2_A2") (pintype "bidirectional"))
      (node (ref "X1") (pin "2") (pinfunction "S_2") (pintype "passive"))
    )
    (net (code "66") (name "V_DIS") (class "Default")
      (node (ref "IC2") (pin "3") (pinfunction "SDA_3") (pintype "input"))
      (node (ref "R26") (pin "1") (pinfunction "1_1") (pintype "passive"))
      (node (ref "U2") (pin "24") (pinfunction "SDA/2_24") (pintype "bidirectional"))
    )
    (net (code "67") (name "V_SCK") (class "Default")
      (node (ref "IC2") (pin "2") (pinfunction "SCL_2") (pintype "input"))
      (node (ref "R28") (pin "1") (pinfunction "1_1") (pintype "passive"))
      (node (ref "U2") (pin "25") (pinfunction "SCL/3_25") (pintype "bidirectional"))
    )
    (net (code "68") (name "Y") (class "Default")
      (node (ref "R6") (pin "2") (pinfunction "2_2") (pintype "passive"))
    )
    (net (code "69") (name "YA") (class "Default")
      (node (ref "CT2") (pin "2") (pinfunction "S1.2_2") (pintype "passive"))
      (node (ref "D3") (pin "A") (pinfunction "A_A") (pintype "passive"))
      (node (ref "D4") (pin "C") (pinfunction "C_C") (pintype "passive"))
      (node (ref "R21") (pin "1") (pinfunction "1_1") (pintype "passive"))
      (node (ref "U2") (pin "8") (pinfunction "14/A2_8") (pintype "bidirectional"))
    )
    (net (code "70") (name "YV") (class "Default")
      (node (ref "R13") (pin "1") (pinfunction "1_1") (pintype "passive"))
      (node (ref "R17") (pin "1") (pinfunction "1_1") (pintype "passive"))
      (node (ref "R18") (pin "1") (pinfunction "1_1") (pintype "passive"))
      (node (ref "U2") (pin "11") (pinfunction "17/A5_11") (pintype "bidirectional"))
    )
    (net (code "71") (name "Y_LED") (class "Default")
      (node (ref "LED5") (pin "A") (pinfunction "A_A") (pintype "passive"))
      (node (ref "LED8") (pin "A") (pinfunction "A_A") (pintype "passive"))
      (node (ref "U2") (pin "27") (pinfunction "MISO/5_27") (pintype "bidirectional"))
    )
    (net (code "72") (name "unconnected-(IC2-DIG4-Pad7)") (class "Default")
      (node (ref "IC2") (pin "7") (pinfunction "DIG4_7") (pintype "bidirectional"))
    )
    (net (code "73") (name "unconnected-(IC3-DIG4-Pad7)") (class "Default")
      (node (ref "IC3") (pin "7") (pinfunction "DIG4_7") (pintype "bidirectional"))
    )
    (net (code "74") (name "unconnected-(RL1-MAIN-Pad11)") (class "Default")
      (node (ref "RL1") (pin "11") (pinfunction "MAIN_11") (pintype "bidirectional"))
    )
    (net (code "75") (name "unconnected-(RL1-N0-Pad14)") (class "Default")
      (node (ref "RL1") (pin "14") (pinfunction "N0_14") (pintype "bidirectional"))
    )
    (net (code "76") (name "unconnected-(RL2-MAIN-Pad11)") (class "Default")
      (node (ref "RL2") (pin "11") (pinfunction "MAIN_11") (pintype "bidirectional"))
    )
    (net (code "77") (name "unconnected-(RL2-N0-Pad14)") (class "Default")
      (node (ref "RL2") (pin "14") (pinfunction "N0_14") (pintype "bidirectional"))
    )
    (net (code "78") (name "unconnected-(RL3-MAIN-Pad11)") (class "Default")
      (node (ref "RL3") (pin "11") (pinfunction "MAIN_11") (pintype "bidirectional"))
    )
    (net (code "79") (name "unconnected-(RL3-N0-Pad14)") (class "Default")
      (node (ref "RL3") (pin "14") (pinfunction "N0_14") (pintype "bidirectional"))
    )
  )
)
